# IMU.net
KiCad netlist of a schematic drawn in Altium Designer
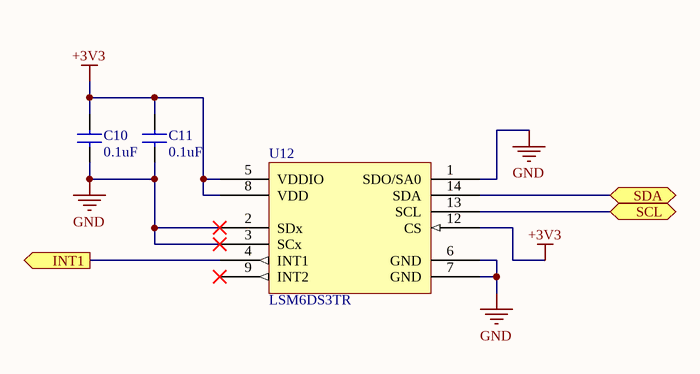
[diagram p0: IMU.SchDoc]

(export (version "E")
  (design (tool "Eeschema 10.0.6"))
  (components
    (comp (ref "C10")
      (value "0.1uF")
      (footprint "0402_CAPACITOR")
      (description "CAP CERM 0.1uF 10% 16V 0402")
      (fields (field (name "VOLTAGE") "16V") (field (name "Comment") "CAP 0.1uF 16V X7R"))
      (libsource (lib "capacitor") (part "C_0402_0.1uF_16V_10%"))
    )
    (comp (ref "C11")
      (value "0.1uF")
      (footprint "0402_CAPACITOR")
      (description "CAP CERM 0.1uF 10% 16V 0402")
      (fields (field (name "VOLTAGE") "16V") (field (name "Comment") "CAP 0.1uF 16V X7R"))
      (libsource (lib "capacitor") (part "C_0402_0.1uF_16V_10%"))
    )
    (comp (ref "U12")
      (value "LSM6DS3TR")
      (footprint "LGA-14_2.5x3mm")
      (description "Accelerometer, Gyroscope, Temperature, 3 Axis Sensor I²C, SPI Output")
      (libsource (lib "ic") (part "U_LSM6DS3"))
    )
  )
  (nets
    (net (code "1") (name "+3V3") (class "Default")
      (node (ref "C10") (pin "2") (pinfunction "2_2") (pintype "passive"))
      (node (ref "C11") (pin "2") (pinfunction "2_2") (pintype "passive"))
      (node (ref "U12") (pin "12") (pinfunction "CS_12") (pintype "input"))
      (node (ref "U12") (pin "5") (pinfunction "VDDIO_5") (pintype "power_in"))
      (node (ref "U12") (pin "8") (pinfunction "VDD_8") (pintype "power_in"))
    )
    (net (code "2") (name "/INT1") (class "Default")
      (node (ref "U12") (pin "4") (pinfunction "INT1_4") (pintype "output"))
    )
    (net (code "3") (name "/SCL") (class "Default")
      (node (ref "U12") (pin "13") (pinfunction "SCL_13") (pintype "passive"))
    )
    (net (code "4") (name "/SDA") (class "Default")
      (node (ref "U12") (pin "14") (pinfunction "SDA_14") (pintype "passive"))
    )
    (net (code "5") (name "GND") (class "Default")
      (node (ref "C10") (pin "1") (pinfunction "1_1") (pintype "passive"))
      (node (ref "C11") (pin "1") (pinfunction "1_1") (pintype "passive"))
      (node (ref "U12") (pin "1") (pinfunction "SDO/SA0_1") (pintype "passive"))
      (node (ref "U12") (pin "2") (pinfunction "SDx_2") (pintype "open_collector"))
      (node (ref "U12") (pin "3") (pinfunction "SCx_3") (pintype "open_collector"))
      (node (ref "U12") (pin "6") (pinfunction "GND_6") (pintype "power_in"))
      (node (ref "U12") (pin "7") (pinfunction "GND_7") (pintype "power_in"))
    )
    (net (code "6") (name "unconnected-(U12-INT2-Pad9)") (class "Default")
      (node (ref "U12") (pin "9") (pinfunction "INT2_9") (pintype "output+no_connect"))
    )
  )
)
